# pca10156_sheet1_connections.net
KiCad netlist of a schematic drawn in Altium Designer
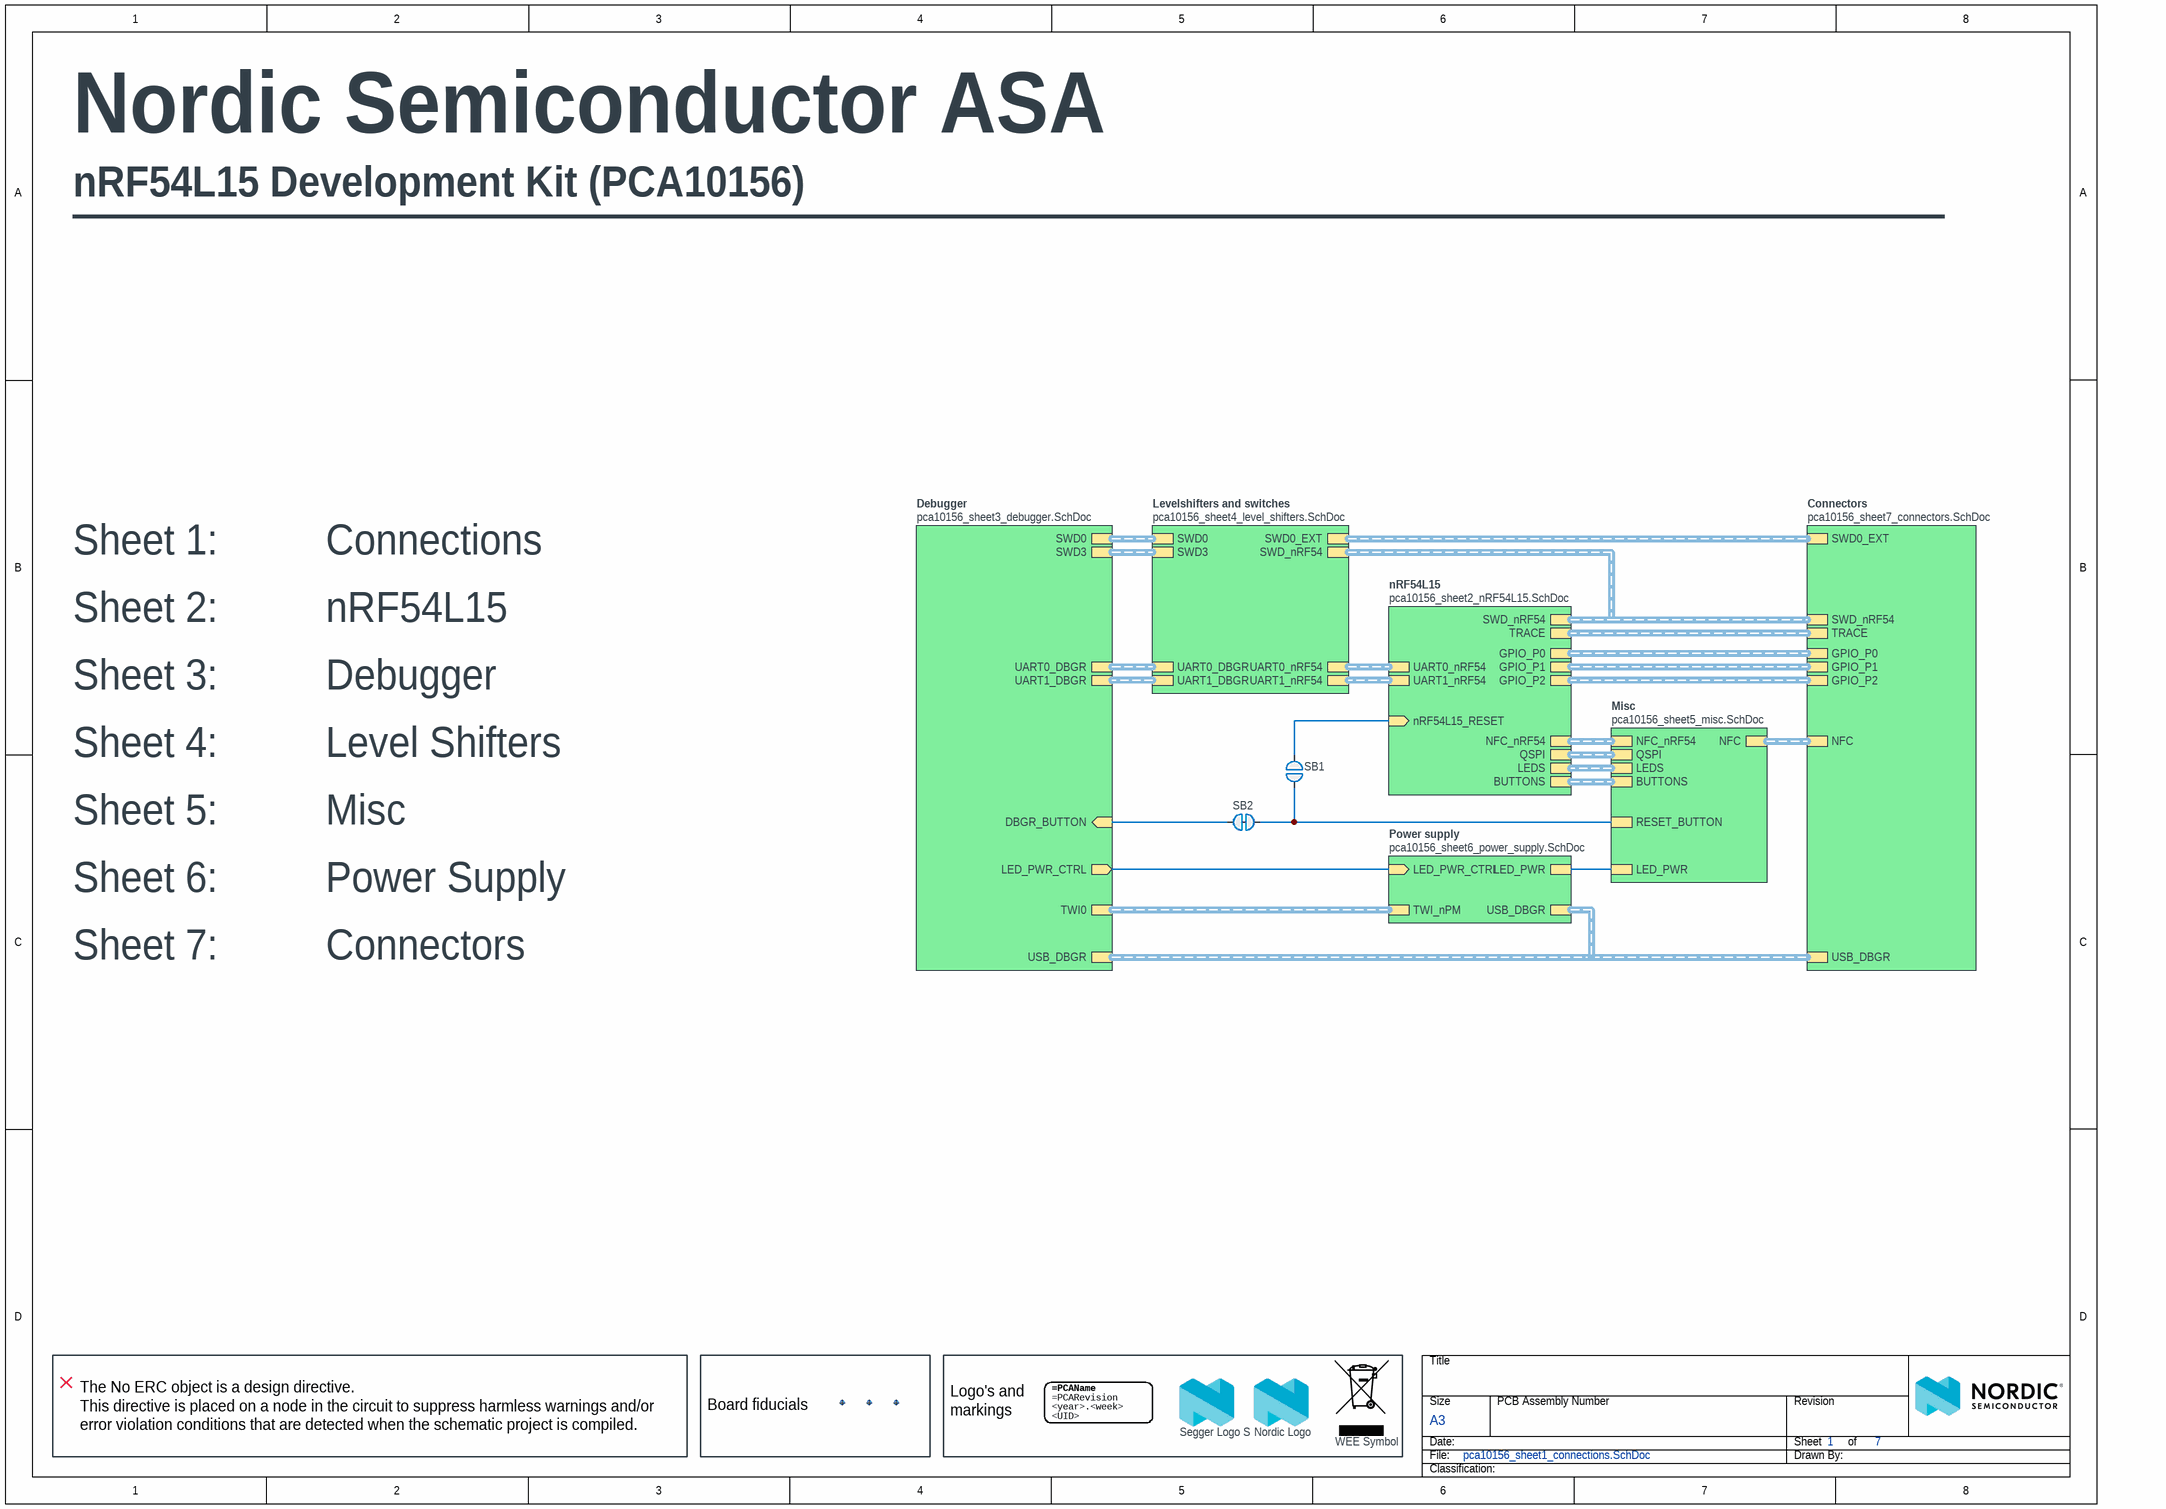
[diagram p0: pca10156_sheet1_connections.SchDoc]

(export (version "E")
  (design (tool "Eeschema 10.0.6"))
  (components
    (comp (ref "Fid1")
      (value "Fiducial mark")
      (footprint "Fiducial")
      (description "Fiducial Mark")
      (fields
        (field (name "PART NUMBER") "Fid-Mark")
        (field (name "MANUFACTURER") "N.A.")
        (field (name "AUTHOR") "rsk")
      )
      (libsource (lib "AltiumLib") (part "Fiducial"))
    )
    (comp (ref "Fid2")
      (value "Fiducial mark")
      (footprint "Fiducial")
      (description "Fiducial Mark")
      (fields
        (field (name "PART NUMBER") "Fid-Mark")
        (field (name "MANUFACTURER") "N.A.")
        (field (name "AUTHOR") "rsk")
      )
      (libsource (lib "AltiumLib") (part "Fiducial"))
    )
    (comp (ref "Fid3")
      (value "Fiducial mark")
      (footprint "Fiducial")
      (description "Fiducial Mark")
      (fields
        (field (name "PART NUMBER") "Fid-Mark")
        (field (name "MANUFACTURER") "N.A.")
        (field (name "AUTHOR") "rsk")
      )
      (libsource (lib "AltiumLib") (part "Fiducial"))
    )
    (comp (ref "LABEL1")
      (value "12x12mm")
      (footprint "LabelSilk_12x12")
      (description "PCA version label, stick-on, 12x12mm")
      (fields
        (field (name "PART NUMBER") "Label_12x12")
        (field (name "MANUFACTURER") "Ellco Etikett")
        (field (name "AUTHOR") "hany")
      )
      (libsource (lib "AltiumLib") (part "Label_Stick-on-4-lines"))
    )
    (comp (ref "LOGO1")
      (value "Nordic Logo")
      (footprint "NORDIC_LOGO_LYING")
      (description "Nordic logo lying")
      (fields
        (field (name "PART NUMBER") "Nordic Logo lying")
        (field (name "MANUFACTURER") "N.A.")
        (field (name "AUTHOR") "rsk")
      )
      (libsource (lib "AltiumLib") (part "Nordic Logo"))
    )
    (comp (ref "LOGO2")
      (value "WEE Symbol")
      (footprint "WEE_3x4.5mm")
      (description "WEEE Directive symbol")
      (fields
        (field (name "PART NUMBER") "WEEE Symbol 3x4.5mm")
        (field (name "MANUFACTURER") "N.A.")
        (field (name "AUTHOR") "rsk")
      )
      (libsource (lib "AltiumLib") (part "WEEE Directive Logo"))
    )
    (comp (ref "LOGO3")
      (value "Segger Logo S")
      (footprint "SEGGER_LOGO_S")
      (description "Segger logo, small size")
      (fields (field (name "MANUFACTURER") "N.A.") (field (name "AUTHOR") "rsk"))
      (libsource (lib "AltiumLib") (part "Nordic Logo"))
    )
    (comp (ref "SB1")
      (value "Solderbridge")
      (footprint "Solderbridge")
      (fields (field (name "MANUFACTURER") "N.A.") (field (name "AUTHOR") "rsk"))
      (libsource (lib "AltiumLib") (part "SOLDERBRIDGE"))
    )
    (comp (ref "SB2")
      (value "Solderbridge")
      (footprint "Solderbridge_Shorted")
      (description "Shorted Solderbridge")
      (fields
        (field (name "PART NUMBER") "Solderbridge Shorted")
        (field (name "MANUFACTURER") "N.A.")
        (field (name "AUTHOR") "rsk")
      )
      (libsource (lib "AltiumLib") (part "SOLDERBRIDGE_SHORTED"))
    )
  )
  (nets
    (net (code "2") (name "/DBGR_BUTTON") (class "Default")
      (node (ref "SB2") (pin "2") (pinfunction "1_2") (pintype "passive"))
    )
    (net (code "12") (name "/RESET_BUTTON") (class "Default")
      (node (ref "SB1") (pin "2") (pinfunction "1_2") (pintype "passive"))
      (node (ref "SB2") (pin "1") (pinfunction "0_1") (pintype "passive"))
    )
    (net (code "24") (name "/nRF54L15_RESET") (class "Default")
      (node (ref "SB1") (pin "1") (pinfunction "0_1") (pintype "passive"))
    )
  )
)
